# Key.net
KiCad netlist of a schematic drawn in Altium Designer
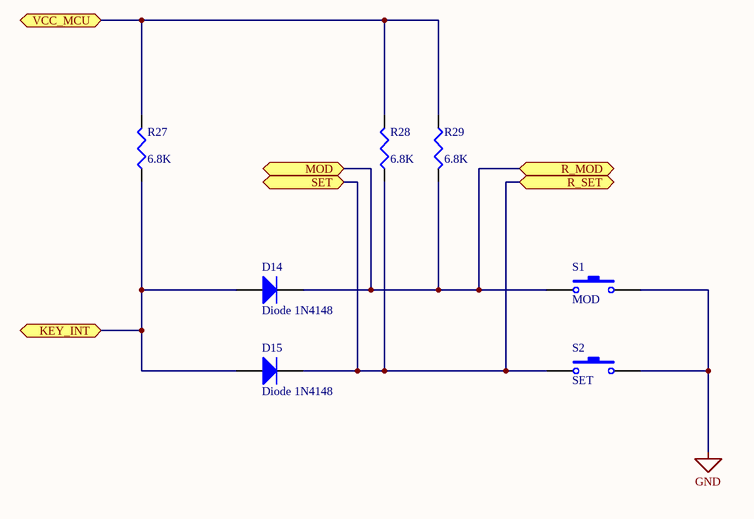
[diagram p0: Key.SchDoc]

(export (version "E")
  (design (tool "Eeschema 10.0.6"))
  (components
    (comp (ref "D14")
      (value "Diode 1N4148")
      (footprint "DO-41")
      (description "1 Amp General Purpose Rectifier")
      (fields (field (name "PUBLISHER") "Altium Limited"))
      (libsource (lib "Miscellaneous Devices") (part "Diode 1N4005"))
    )
    (comp (ref "D15")
      (value "Diode 1N4148")
      (footprint "DO-41")
      (description "1 Amp General Purpose Rectifier")
      (fields (field (name "PUBLISHER") "Altium Limited"))
      (libsource (lib "Miscellaneous Devices") (part "Diode 1N4005"))
    )
    (comp (ref "R27")
      (value "6.8K")
      (footprint "12Z-2010")
      (description "Resistor")
      (fields (field (name "Comment") "Res3") (field (name "PUBLISHER") "Altium Limited"))
      (libsource (lib "Miscellaneous Devices") (part "Res3"))
    )
    (comp (ref "R28")
      (value "6.8K")
      (footprint "12Z-2010")
      (description "Resistor")
      (fields (field (name "Comment") "Res3") (field (name "PUBLISHER") "Altium Limited"))
      (libsource (lib "Miscellaneous Devices") (part "Res3"))
    )
    (comp (ref "R29")
      (value "6.8K")
      (footprint "12Z-2010")
      (description "Resistor")
      (fields (field (name "Comment") "Res3") (field (name "PUBLISHER") "Altium Limited"))
      (libsource (lib "Miscellaneous Devices") (part "Res3"))
    )
    (comp (ref "S1")
      (value "MOD")
      (footprint "SPST-2")
      (description "Switch")
      (fields (field (name "PUBLISHER") "Altium Limited"))
      (libsource (lib "Miscellaneous Devices") (part "SW-PB"))
    )
    (comp (ref "S2")
      (value "SET")
      (footprint "SPST-2")
      (description "Switch")
      (fields (field (name "PUBLISHER") "Altium Limited"))
      (libsource (lib "Miscellaneous Devices") (part "SW-PB"))
    )
  )
  (nets
    (net (code "1") (name "/KEY_INT") (class "Default")
      (node (ref "D14") (pin "1") (pinfunction "A_1") (pintype "passive"))
      (node (ref "D15") (pin "1") (pinfunction "A_1") (pintype "passive"))
      (node (ref "R27") (pin "1") (pinfunction "1_1") (pintype "passive"))
    )
    (net (code "2") (name "/MOD") (class "Default")
      (node (ref "D14") (pin "2") (pinfunction "K_2") (pintype "passive"))
      (node (ref "R29") (pin "2") (pinfunction "2_2") (pintype "passive"))
      (node (ref "S1") (pin "1") (pinfunction "1_1") (pintype "passive"))
    )
    (net (code "3") (name "/R_SET") (class "Default")
      (node (ref "D15") (pin "2") (pinfunction "K_2") (pintype "passive"))
      (node (ref "R28") (pin "1") (pinfunction "1_1") (pintype "passive"))
      (node (ref "S2") (pin "1") (pinfunction "1_1") (pintype "passive"))
    )
    (net (code "4") (name "/VCC_MCU") (class "Default")
      (node (ref "R27") (pin "2") (pinfunction "2_2") (pintype "passive"))
      (node (ref "R28") (pin "2") (pinfunction "2_2") (pintype "passive"))
      (node (ref "R29") (pin "1") (pinfunction "1_1") (pintype "passive"))
    )
    (net (code "5") (name "GND") (class "Default")
      (node (ref "S1") (pin "2") (pinfunction "2_2") (pintype "passive"))
      (node (ref "S2") (pin "2") (pinfunction "2_2") (pintype "passive"))
    )
  )
)
